# serre_light_v1.net
KiCad netlist of a schematic drawn in EAGLE
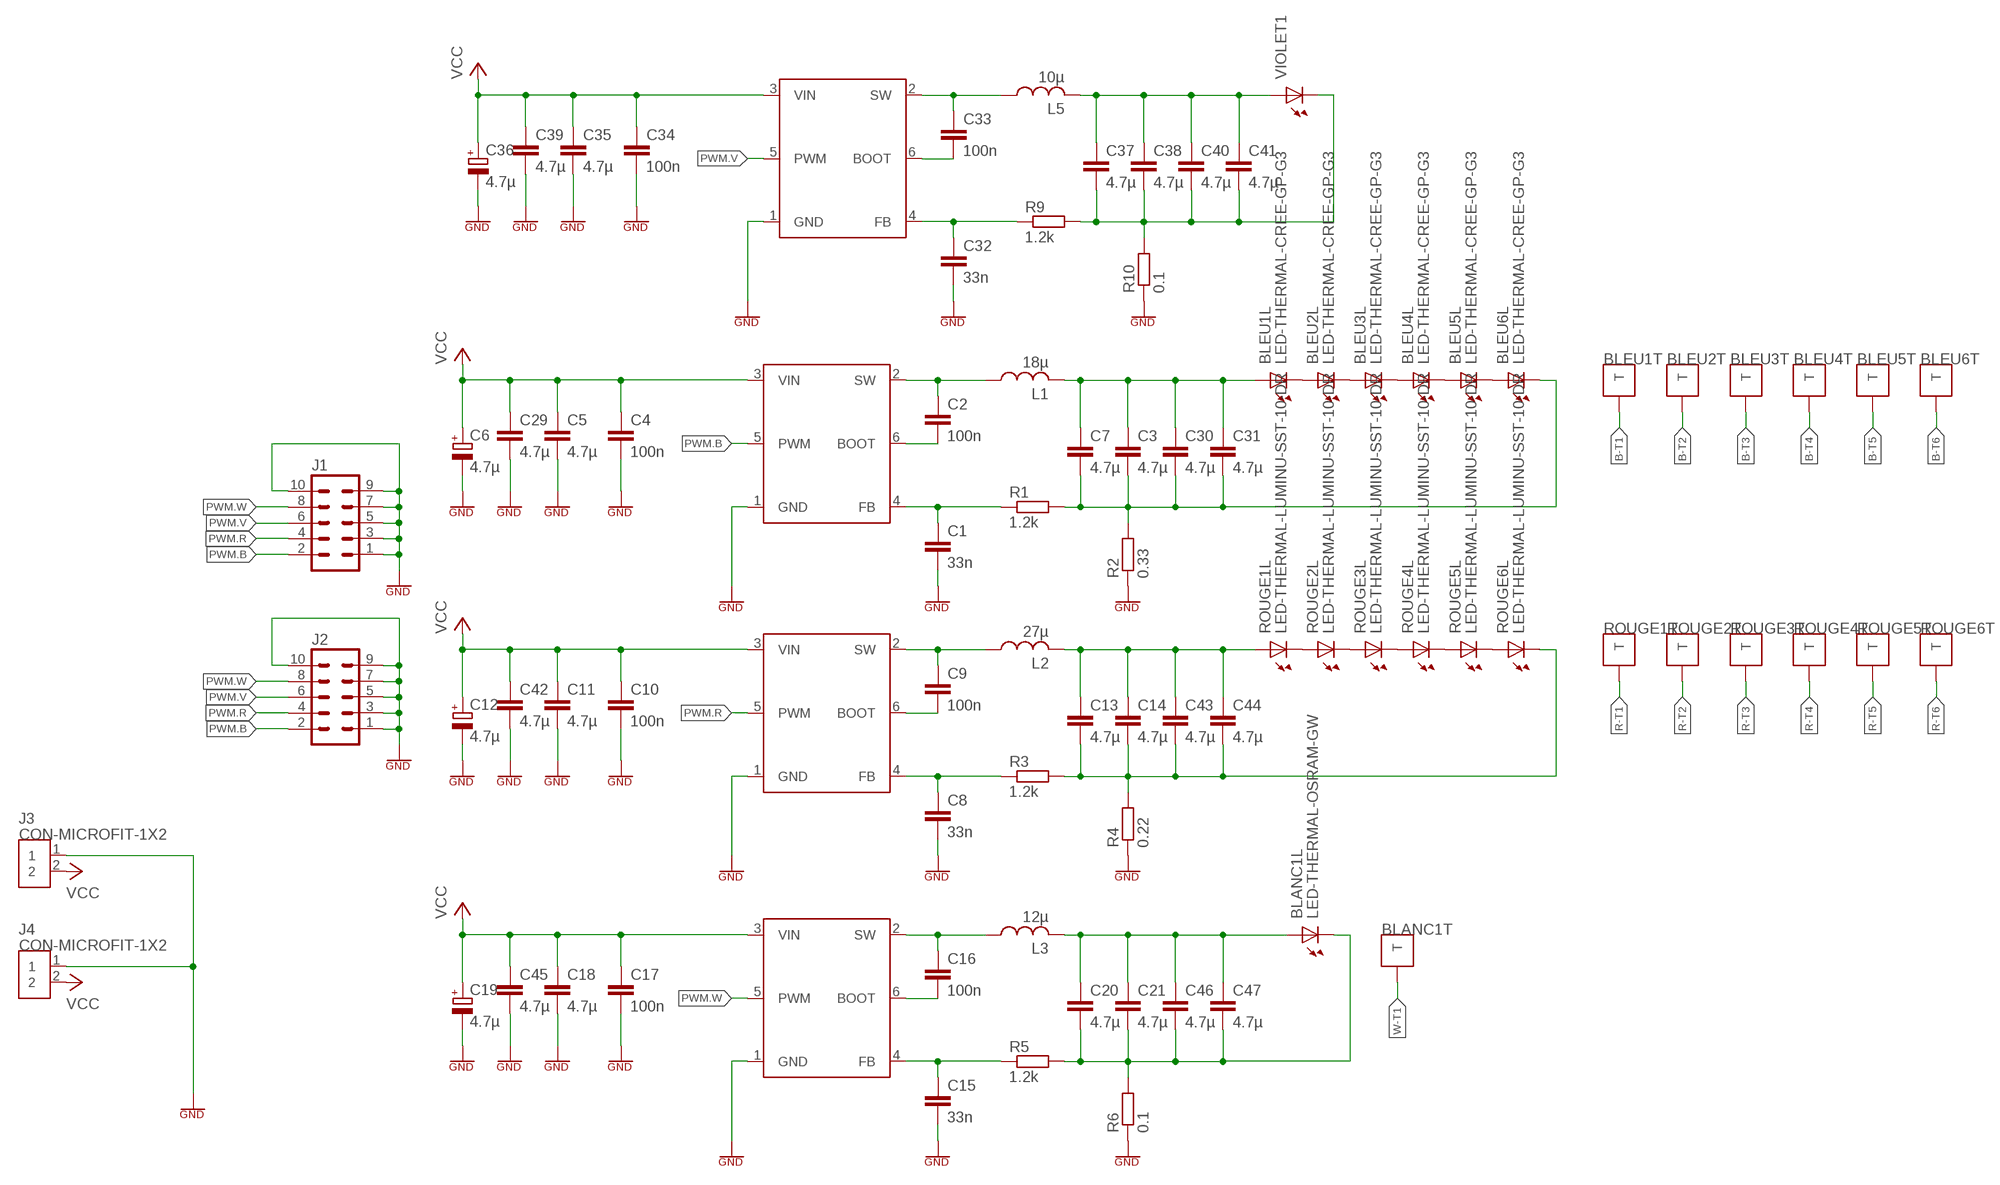
[diagram p0: schematic, sheet 1]

(export (version "E")
  (design (tool "Eeschema 10.0.6"))
  (components
    (comp (ref "BLANC1")
      (value "LED-THERMAL-OSRAM-GW")
      (footprint "eagle-import:LED-OSRAM-GW")
      (libsource (lib "eagle-import") (part "LED-THERMAL-OSRAM-GW"))
    )
    (comp (ref "BLEU1")
      (value "LED-THERMAL-CREE-GP-G3")
      (footprint "eagle-import:LED-CREE-GP-G3")
      (libsource (lib "eagle-import") (part "LED-THERMAL-CREE-GP-G3"))
    )
    (comp (ref "BLEU2")
      (value "LED-THERMAL-CREE-GP-G3")
      (footprint "eagle-import:LED-CREE-GP-G3")
      (libsource (lib "eagle-import") (part "LED-THERMAL-CREE-GP-G3"))
    )
    (comp (ref "BLEU3")
      (value "LED-THERMAL-CREE-GP-G3")
      (footprint "eagle-import:LED-CREE-GP-G3")
      (libsource (lib "eagle-import") (part "LED-THERMAL-CREE-GP-G3"))
    )
    (comp (ref "BLEU4")
      (value "LED-THERMAL-CREE-GP-G3")
      (footprint "eagle-import:LED-CREE-GP-G3")
      (libsource (lib "eagle-import") (part "LED-THERMAL-CREE-GP-G3"))
    )
    (comp (ref "BLEU5")
      (value "LED-THERMAL-CREE-GP-G3")
      (footprint "eagle-import:LED-CREE-GP-G3")
      (libsource (lib "eagle-import") (part "LED-THERMAL-CREE-GP-G3"))
    )
    (comp (ref "BLEU6")
      (value "LED-THERMAL-CREE-GP-G3")
      (footprint "eagle-import:LED-CREE-GP-G3")
      (libsource (lib "eagle-import") (part "LED-THERMAL-CREE-GP-G3"))
    )
    (comp (ref "C1")
      (value "33n")
      (footprint "eagle-import:C0603")
      (libsource (lib "eagle-import") (part "CC0603"))
    )
    (comp (ref "C2")
      (value "100n")
      (footprint "eagle-import:C0603")
      (libsource (lib "eagle-import") (part "CC0603"))
    )
    (comp (ref "C3")
      (value "4.7µ")
      (footprint "eagle-import:C1210")
      (libsource (lib "eagle-import") (part "C-EUC1210"))
    )
    (comp (ref "C4")
      (value "100n")
      (footprint "eagle-import:C0805")
      (libsource (lib "eagle-import") (part "CC0805"))
    )
    (comp (ref "C5")
      (value "4.7µ")
      (footprint "eagle-import:C1210")
      (libsource (lib "eagle-import") (part "C-EUC1210"))
    )
    (comp (ref "C6")
      (value "4.7µ")
      (footprint "eagle-import:CAP-TANT-B")
      (libsource (lib "eagle-import") (part "CPOL-B"))
    )
    (comp (ref "C7")
      (value "4.7µ")
      (footprint "eagle-import:C1210")
      (libsource (lib "eagle-import") (part "C-EUC1210"))
    )
    (comp (ref "C8")
      (value "33n")
      (footprint "eagle-import:C0603")
      (libsource (lib "eagle-import") (part "CC0603"))
    )
    (comp (ref "C9")
      (value "100n")
      (footprint "eagle-import:C0603")
      (libsource (lib "eagle-import") (part "CC0603"))
    )
    (comp (ref "C10")
      (value "100n")
      (footprint "eagle-import:C0805")
      (libsource (lib "eagle-import") (part "CC0805"))
    )
    (comp (ref "C11")
      (value "4.7µ")
      (footprint "eagle-import:C1210")
      (libsource (lib "eagle-import") (part "C-EUC1210"))
    )
    (comp (ref "C12")
      (value "4.7µ")
      (footprint "eagle-import:CAP-TANT-B")
      (libsource (lib "eagle-import") (part "CPOL-B"))
    )
    (comp (ref "C13")
      (value "4.7µ")
      (footprint "eagle-import:C1210")
      (libsource (lib "eagle-import") (part "C-EUC1210"))
    )
    (comp (ref "C14")
      (value "4.7µ")
      (footprint "eagle-import:C1210")
      (libsource (lib "eagle-import") (part "C-EUC1210"))
    )
    (comp (ref "C15")
      (value "33n")
      (footprint "eagle-import:C0603")
      (libsource (lib "eagle-import") (part "CC0603"))
    )
    (comp (ref "C16")
      (value "100n")
      (footprint "eagle-import:C0603")
      (libsource (lib "eagle-import") (part "CC0603"))
    )
    (comp (ref "C17")
      (value "100n")
      (footprint "eagle-import:C0805")
      (libsource (lib "eagle-import") (part "CC0805"))
    )
    (comp (ref "C18")
      (value "4.7µ")
      (footprint "eagle-import:C1210")
      (libsource (lib "eagle-import") (part "C-EUC1210"))
    )
    (comp (ref "C19")
      (value "4.7µ")
      (footprint "eagle-import:CAP-TANT-B")
      (libsource (lib "eagle-import") (part "CPOL-B"))
    )
    (comp (ref "C20")
      (value "4.7µ")
      (footprint "eagle-import:C1210")
      (libsource (lib "eagle-import") (part "C-EUC1210"))
    )
    (comp (ref "C21")
      (value "4.7µ")
      (footprint "eagle-import:C1210")
      (libsource (lib "eagle-import") (part "C-EUC1210"))
    )
    (comp (ref "C29")
      (value "4.7µ")
      (footprint "eagle-import:C1210")
      (libsource (lib "eagle-import") (part "C-EUC1210"))
    )
    (comp (ref "C30")
      (value "4.7µ")
      (footprint "eagle-import:C1210")
      (libsource (lib "eagle-import") (part "C-EUC1210"))
    )
    (comp (ref "C31")
      (value "4.7µ")
      (footprint "eagle-import:C1210")
      (libsource (lib "eagle-import") (part "C-EUC1210"))
    )
    (comp (ref "C32")
      (value "33n")
      (footprint "eagle-import:C0603")
      (libsource (lib "eagle-import") (part "CC0603"))
    )
    (comp (ref "C33")
      (value "100n")
      (footprint "eagle-import:C0603")
      (libsource (lib "eagle-import") (part "CC0603"))
    )
    (comp (ref "C34")
      (value "100n")
      (footprint "eagle-import:C0805")
      (libsource (lib "eagle-import") (part "CC0805"))
    )
    (comp (ref "C35")
      (value "4.7µ")
      (footprint "eagle-import:C1210")
      (libsource (lib "eagle-import") (part "C-EUC1210"))
    )
    (comp (ref "C36")
      (value "4.7µ")
      (footprint "eagle-import:CAP-TANT-B")
      (libsource (lib "eagle-import") (part "CPOL-B"))
    )
    (comp (ref "C37")
      (value "4.7µ")
      (footprint "eagle-import:C1210")
      (libsource (lib "eagle-import") (part "C-EUC1210"))
    )
    (comp (ref "C38")
      (value "4.7µ")
      (footprint "eagle-import:C1210")
      (libsource (lib "eagle-import") (part "C-EUC1210"))
    )
    (comp (ref "C39")
      (value "4.7µ")
      (footprint "eagle-import:C1210")
      (libsource (lib "eagle-import") (part "C-EUC1210"))
    )
    (comp (ref "C40")
      (value "4.7µ")
      (footprint "eagle-import:C1210")
      (libsource (lib "eagle-import") (part "C-EUC1210"))
    )
    (comp (ref "C41")
      (value "4.7µ")
      (footprint "eagle-import:C1210")
      (libsource (lib "eagle-import") (part "C-EUC1210"))
    )
    (comp (ref "C42")
      (value "4.7µ")
      (footprint "eagle-import:C1210")
      (libsource (lib "eagle-import") (part "C-EUC1210"))
    )
    (comp (ref "C43")
      (value "4.7µ")
      (footprint "eagle-import:C1210")
      (libsource (lib "eagle-import") (part "C-EUC1210"))
    )
    (comp (ref "C44")
      (value "4.7µ")
      (footprint "eagle-import:C1210")
      (libsource (lib "eagle-import") (part "C-EUC1210"))
    )
    (comp (ref "C45")
      (value "4.7µ")
      (footprint "eagle-import:C1210")
      (libsource (lib "eagle-import") (part "C-EUC1210"))
    )
    (comp (ref "C46")
      (value "4.7µ")
      (footprint "eagle-import:C1210")
      (libsource (lib "eagle-import") (part "C-EUC1210"))
    )
    (comp (ref "C47")
      (value "4.7µ")
      (footprint "eagle-import:C1210")
      (libsource (lib "eagle-import") (part "C-EUC1210"))
    )
    (comp (ref "IC1")
      (value "TPS54201")
      (footprint "eagle-import:SOT23-6")
      (libsource (lib "eagle-import") (part "TPS54201"))
    )
    (comp (ref "IC2")
      (value "TPS54201")
      (footprint "eagle-import:SOT23-6")
      (libsource (lib "eagle-import") (part "TPS54201"))
    )
    (comp (ref "IC3")
      (value "TPS54201")
      (footprint "eagle-import:SOT23-6")
      (libsource (lib "eagle-import") (part "TPS54201"))
    )
    (comp (ref "IC5")
      (value "TPS54201")
      (footprint "eagle-import:SOT23-6")
      (libsource (lib "eagle-import") (part "TPS54201"))
    )
    (comp (ref "J1")
      (value "ML10")
      (footprint "eagle-import:ML10")
      (libsource (lib "eagle-import") (part "ML10"))
    )
    (comp (ref "J2")
      (value "ML10")
      (footprint "eagle-import:ML10")
      (libsource (lib "eagle-import") (part "ML10"))
    )
    (comp (ref "J3")
      (value "CON-MICROFIT-1X2")
      (footprint "eagle-import:MICROFIT-1X2")
      (libsource (lib "eagle-import") (part "CON-MICROFIT-1X2"))
    )
    (comp (ref "J4")
      (value "CON-MICROFIT-1X2")
      (footprint "eagle-import:MICROFIT-1X2")
      (libsource (lib "eagle-import") (part "CON-MICROFIT-1X2"))
    )
    (comp (ref "L1")
      (value "18µ")
      (footprint "eagle-import:L-COILCRAFT-MSS1038")
      (libsource (lib "eagle-import") (part "L-MSS1038"))
    )
    (comp (ref "L2")
      (value "27µ")
      (footprint "eagle-import:L-COILCRAFT-MSS1038")
      (libsource (lib "eagle-import") (part "L-MSS1038"))
    )
    (comp (ref "L3")
      (value "12µ")
      (footprint "eagle-import:L-COILCRAFT-MSS1038")
      (libsource (lib "eagle-import") (part "L-MSS1038"))
    )
    (comp (ref "L5")
      (value "10µ")
      (footprint "eagle-import:L-COILCRAFT-MSS1038")
      (libsource (lib "eagle-import") (part "L-MSS1038"))
    )
    (comp (ref "R1")
      (value "1.2k")
      (footprint "eagle-import:R0805")
      (libsource (lib "eagle-import") (part "RR0805"))
    )
    (comp (ref "R2")
      (value "0.33")
      (footprint "eagle-import:R1206")
      (libsource (lib "eagle-import") (part "R-EU_R1206"))
    )
    (comp (ref "R3")
      (value "1.2k")
      (footprint "eagle-import:R0805")
      (libsource (lib "eagle-import") (part "RR0805"))
    )
    (comp (ref "R4")
      (value "0.22")
      (footprint "eagle-import:R1206")
      (libsource (lib "eagle-import") (part "R-EU_R1206"))
    )
    (comp (ref "R5")
      (value "1.2k")
      (footprint "eagle-import:R0805")
      (libsource (lib "eagle-import") (part "RR0805"))
    )
    (comp (ref "R6")
      (value "0.1")
      (footprint "eagle-import:R1206")
      (libsource (lib "eagle-import") (part "R-EU_R1206"))
    )
    (comp (ref "R9")
      (value "1.2k")
      (footprint "eagle-import:R0805")
      (libsource (lib "eagle-import") (part "RR0805"))
    )
    (comp (ref "R10")
      (value "0.1")
      (footprint "eagle-import:R1206")
      (libsource (lib "eagle-import") (part "R-EU_R1206"))
    )
    (comp (ref "ROUGE1")
      (value "LED-THERMAL-LUMINU-SST-10-DR")
      (footprint "eagle-import:LED-LUMINU-SST-10-DR")
      (libsource (lib "eagle-import") (part "LED-THERMAL-LUMINU-SST-10-DR"))
    )
    (comp (ref "ROUGE2")
      (value "LED-THERMAL-LUMINU-SST-10-DR")
      (footprint "eagle-import:LED-LUMINU-SST-10-DR")
      (libsource (lib "eagle-import") (part "LED-THERMAL-LUMINU-SST-10-DR"))
    )
    (comp (ref "ROUGE3")
      (value "LED-THERMAL-LUMINU-SST-10-DR")
      (footprint "eagle-import:LED-LUMINU-SST-10-DR")
      (libsource (lib "eagle-import") (part "LED-THERMAL-LUMINU-SST-10-DR"))
    )
    (comp (ref "ROUGE4")
      (value "LED-THERMAL-LUMINU-SST-10-DR")
      (footprint "eagle-import:LED-LUMINU-SST-10-DR")
      (libsource (lib "eagle-import") (part "LED-THERMAL-LUMINU-SST-10-DR"))
    )
    (comp (ref "ROUGE5")
      (value "LED-THERMAL-LUMINU-SST-10-DR")
      (footprint "eagle-import:LED-LUMINU-SST-10-DR")
      (libsource (lib "eagle-import") (part "LED-THERMAL-LUMINU-SST-10-DR"))
    )
    (comp (ref "ROUGE6")
      (value "LED-THERMAL-LUMINU-SST-10-DR")
      (footprint "eagle-import:LED-LUMINU-SST-10-DR")
      (libsource (lib "eagle-import") (part "LED-THERMAL-LUMINU-SST-10-DR"))
    )
    (comp (ref "VIOLET1")
      (value "LED-LUXEON-UV-U2")
      (footprint "eagle-import:LED-LUXEON-UV-U2")
      (libsource (lib "eagle-import") (part "LED-LUXEON-UV-U2"))
    )
  )
  (nets
    (net (code "1") (name "B-T1") (class "Default")
      (node (ref "BLEU1") (pin "THERMAL") (pinfunction "T_THERMAL") (pintype "bidirectional"))
    )
    (net (code "2") (name "B-T2") (class "Default")
      (node (ref "BLEU2") (pin "THERMAL") (pinfunction "T_THERMAL") (pintype "bidirectional"))
    )
    (net (code "3") (name "B-T3") (class "Default")
      (node (ref "BLEU3") (pin "THERMAL") (pinfunction "T_THERMAL") (pintype "bidirectional"))
    )
    (net (code "4") (name "B-T4") (class "Default")
      (node (ref "BLEU4") (pin "THERMAL") (pinfunction "T_THERMAL") (pintype "bidirectional"))
    )
    (net (code "5") (name "B-T5") (class "Default")
      (node (ref "BLEU5") (pin "THERMAL") (pinfunction "T_THERMAL") (pintype "bidirectional"))
    )
    (net (code "6") (name "B-T6") (class "Default")
      (node (ref "BLEU6") (pin "THERMAL") (pinfunction "T_THERMAL") (pintype "bidirectional"))
    )
    (net (code "7") (name "GND") (class "Default")
      (node (ref "C1") (pin "2") (pinfunction "2_2") (pintype "passive"))
      (node (ref "C10") (pin "2") (pinfunction "2_2") (pintype "passive"))
      (node (ref "C11") (pin "2") (pinfunction "2_2") (pintype "passive"))
      (node (ref "C12") (pin "-") (pinfunction "-_-") (pintype "passive"))
      (node (ref "C15") (pin "2") (pinfunction "2_2") (pintype "passive"))
      (node (ref "C17") (pin "2") (pinfunction "2_2") (pintype "passive"))
      (node (ref "C18") (pin "2") (pinfunction "2_2") (pintype "passive"))
      (node (ref "C19") (pin "-") (pinfunction "-_-") (pintype "passive"))
      (node (ref "C29") (pin "2") (pinfunction "2_2") (pintype "passive"))
      (node (ref "C32") (pin "2") (pinfunction "2_2") (pintype "passive"))
      (node (ref "C34") (pin "2") (pinfunction "2_2") (pintype "passive"))
      (node (ref "C35") (pin "2") (pinfunction "2_2") (pintype "passive"))
      (node (ref "C36") (pin "-") (pinfunction "-_-") (pintype "passive"))
      (node (ref "C39") (pin "2") (pinfunction "2_2") (pintype "passive"))
      (node (ref "C4") (pin "2") (pinfunction "2_2") (pintype "passive"))
      (node (ref "C42") (pin "2") (pinfunction "2_2") (pintype "passive"))
      (node (ref "C45") (pin "2") (pinfunction "2_2") (pintype "passive"))
      (node (ref "C5") (pin "2") (pinfunction "2_2") (pintype "passive"))
      (node (ref "C6") (pin "-") (pinfunction "-_-") (pintype "passive"))
      (node (ref "C8") (pin "2") (pinfunction "2_2") (pintype "passive"))
      (node (ref "IC1") (pin "1") (pinfunction "GND_1") (pintype "bidirectional"))
      (node (ref "IC2") (pin "1") (pinfunction "GND_1") (pintype "bidirectional"))
      (node (ref "IC3") (pin "1") (pinfunction "GND_1") (pintype "bidirectional"))
      (node (ref "IC5") (pin "1") (pinfunction "GND_1") (pintype "bidirectional"))
      (node (ref "J1") (pin "1") (pinfunction "1_1") (pintype "passive"))
      (node (ref "J1") (pin "10") (pinfunction "10_10") (pintype "passive"))
      (node (ref "J1") (pin "3") (pinfunction "3_3") (pintype "passive"))
      (node (ref "J1") (pin "5") (pinfunction "5_5") (pintype "passive"))
      (node (ref "J1") (pin "7") (pinfunction "7_7") (pintype "passive"))
      (node (ref "J1") (pin "9") (pinfunction "9_9") (pintype "passive"))
      (node (ref "J2") (pin "1") (pinfunction "1_1") (pintype "passive"))
      (node (ref "J2") (pin "10") (pinfunction "10_10") (pintype "passive"))
      (node (ref "J2") (pin "3") (pinfunction "3_3") (pintype "passive"))
      (node (ref "J2") (pin "5") (pinfunction "5_5") (pintype "passive"))
      (node (ref "J2") (pin "7") (pinfunction "7_7") (pintype "passive"))
      (node (ref "J2") (pin "9") (pinfunction "9_9") (pintype "passive"))
      (node (ref "J3") (pin "1") (pinfunction "1_1") (pintype "bidirectional"))
      (node (ref "J4") (pin "1") (pinfunction "1_1") (pintype "bidirectional"))
      (node (ref "R10") (pin "1") (pinfunction "1_1") (pintype "passive"))
      (node (ref "R2") (pin "1") (pinfunction "1_1") (pintype "passive"))
      (node (ref "R4") (pin "1") (pinfunction "1_1") (pintype "passive"))
      (node (ref "R6") (pin "1") (pinfunction "1_1") (pintype "passive"))
    )
    (net (code "8") (name "Net-(BLANC1-PadA)") (class "Default")
      (node (ref "BLANC1") (pin "A") (pinfunction "A_A") (pintype "passive"))
      (node (ref "C20") (pin "1") (pinfunction "1_1") (pintype "passive"))
      (node (ref "C21") (pin "1") (pinfunction "1_1") (pintype "passive"))
      (node (ref "C46") (pin "1") (pinfunction "1_1") (pintype "passive"))
      (node (ref "C47") (pin "1") (pinfunction "1_1") (pintype "passive"))
      (node (ref "L3") (pin "2") (pinfunction "2_2") (pintype "passive"))
    )
    (net (code "9") (name "Net-(BLANC1-PadC)") (class "Default")
      (node (ref "BLANC1") (pin "C") (pinfunction "C_C") (pintype "passive"))
      (node (ref "C20") (pin "2") (pinfunction "2_2") (pintype "passive"))
      (node (ref "C21") (pin "2") (pinfunction "2_2") (pintype "passive"))
      (node (ref "C46") (pin "2") (pinfunction "2_2") (pintype "passive"))
      (node (ref "C47") (pin "2") (pinfunction "2_2") (pintype "passive"))
      (node (ref "R5") (pin "2") (pinfunction "2_2") (pintype "passive"))
      (node (ref "R6") (pin "2") (pinfunction "2_2") (pintype "passive"))
    )
    (net (code "10") (name "Net-(BLEU1-PadA)") (class "Default")
      (node (ref "BLEU1") (pin "A") (pinfunction "A_A") (pintype "passive"))
      (node (ref "C3") (pin "1") (pinfunction "1_1") (pintype "passive"))
      (node (ref "C30") (pin "1") (pinfunction "1_1") (pintype "passive"))
      (node (ref "C31") (pin "1") (pinfunction "1_1") (pintype "passive"))
      (node (ref "C7") (pin "1") (pinfunction "1_1") (pintype "passive"))
      (node (ref "L1") (pin "2") (pinfunction "2_2") (pintype "passive"))
    )
    (net (code "11") (name "Net-(BLEU1-PadC)") (class "Default")
      (node (ref "BLEU1") (pin "C") (pinfunction "C_C") (pintype "passive"))
      (node (ref "BLEU2") (pin "A") (pinfunction "A_A") (pintype "passive"))
    )
    (net (code "12") (name "Net-(BLEU2-PadC)") (class "Default")
      (node (ref "BLEU2") (pin "C") (pinfunction "C_C") (pintype "passive"))
      (node (ref "BLEU3") (pin "A") (pinfunction "A_A") (pintype "passive"))
    )
    (net (code "13") (name "Net-(BLEU3-PadC)") (class "Default")
      (node (ref "BLEU3") (pin "C") (pinfunction "C_C") (pintype "passive"))
      (node (ref "BLEU4") (pin "A") (pinfunction "A_A") (pintype "passive"))
    )
    (net (code "14") (name "Net-(BLEU4-PadC)") (class "Default")
      (node (ref "BLEU4") (pin "C") (pinfunction "C_C") (pintype "passive"))
      (node (ref "BLEU5") (pin "A") (pinfunction "A_A") (pintype "passive"))
    )
    (net (code "15") (name "Net-(BLEU5-PadC)") (class "Default")
      (node (ref "BLEU5") (pin "C") (pinfunction "C_C") (pintype "passive"))
      (node (ref "BLEU6") (pin "A") (pinfunction "A_A") (pintype "passive"))
    )
    (net (code "16") (name "Net-(BLEU6-PadC)") (class "Default")
      (node (ref "BLEU6") (pin "C") (pinfunction "C_C") (pintype "passive"))
      (node (ref "C3") (pin "2") (pinfunction "2_2") (pintype "passive"))
      (node (ref "C30") (pin "2") (pinfunction "2_2") (pintype "passive"))
      (node (ref "C31") (pin "2") (pinfunction "2_2") (pintype "passive"))
      (node (ref "C7") (pin "2") (pinfunction "2_2") (pintype "passive"))
      (node (ref "R1") (pin "2") (pinfunction "2_2") (pintype "passive"))
      (node (ref "R2") (pin "2") (pinfunction "2_2") (pintype "passive"))
    )
    (net (code "17") (name "Net-(C13-Pad1)") (class "Default")
      (node (ref "C13") (pin "1") (pinfunction "1_1") (pintype "passive"))
      (node (ref "C14") (pin "1") (pinfunction "1_1") (pintype "passive"))
      (node (ref "C43") (pin "1") (pinfunction "1_1") (pintype "passive"))
      (node (ref "C44") (pin "1") (pinfunction "1_1") (pintype "passive"))
      (node (ref "L2") (pin "2") (pinfunction "2_2") (pintype "passive"))
      (node (ref "ROUGE1") (pin "A") (pinfunction "A_A") (pintype "passive"))
    )
    (net (code "18") (name "Net-(C13-Pad2)") (class "Default")
      (node (ref "C13") (pin "2") (pinfunction "2_2") (pintype "passive"))
      (node (ref "C14") (pin "2") (pinfunction "2_2") (pintype "passive"))
      (node (ref "C43") (pin "2") (pinfunction "2_2") (pintype "passive"))
      (node (ref "C44") (pin "2") (pinfunction "2_2") (pintype "passive"))
      (node (ref "R3") (pin "2") (pinfunction "2_2") (pintype "passive"))
      (node (ref "R4") (pin "2") (pinfunction "2_2") (pintype "passive"))
      (node (ref "ROUGE6") (pin "C") (pinfunction "C_C") (pintype "passive"))
    )
    (net (code "19") (name "Net-(C37-Pad1)") (class "Default")
      (node (ref "C37") (pin "1") (pinfunction "1_1") (pintype "passive"))
      (node (ref "C38") (pin "1") (pinfunction "1_1") (pintype "passive"))
      (node (ref "C40") (pin "1") (pinfunction "1_1") (pintype "passive"))
      (node (ref "C41") (pin "1") (pinfunction "1_1") (pintype "passive"))
      (node (ref "L5") (pin "2") (pinfunction "2_2") (pintype "passive"))
      (node (ref "VIOLET1") (pin "A") (pinfunction "A_A") (pintype "passive"))
    )
    (net (code "20") (name "Net-(C37-Pad2)") (class "Default")
      (node (ref "C37") (pin "2") (pinfunction "2_2") (pintype "passive"))
      (node (ref "C38") (pin "2") (pinfunction "2_2") (pintype "passive"))
      (node (ref "C40") (pin "2") (pinfunction "2_2") (pintype "passive"))
      (node (ref "C41") (pin "2") (pinfunction "2_2") (pintype "passive"))
      (node (ref "R10") (pin "2") (pinfunction "2_2") (pintype "passive"))
      (node (ref "R9") (pin "2") (pinfunction "2_2") (pintype "passive"))
      (node (ref "VIOLET1") (pin "C") (pinfunction "C_C") (pintype "passive"))
    )
    (net (code "21") (name "Net-(IC1-BOOT)") (class "Default")
      (node (ref "C2") (pin "2") (pinfunction "2_2") (pintype "passive"))
      (node (ref "IC1") (pin "6") (pinfunction "BOOT_6") (pintype "bidirectional"))
    )
    (net (code "22") (name "Net-(IC1-FB)") (class "Default")
      (node (ref "C1") (pin "1") (pinfunction "1_1") (pintype "passive"))
      (node (ref "IC1") (pin "4") (pinfunction "FB_4") (pintype "bidirectional"))
      (node (ref "R1") (pin "1") (pinfunction "1_1") (pintype "passive"))
    )
    (net (code "23") (name "Net-(IC1-SW)") (class "Default")
      (node (ref "C2") (pin "1") (pinfunction "1_1") (pintype "passive"))
      (node (ref "IC1") (pin "2") (pinfunction "SW_2") (pintype "bidirectional"))
      (node (ref "L1") (pin "1") (pinfunction "1_1") (pintype "passive"))
    )
    (net (code "24") (name "Net-(IC2-BOOT)") (class "Default")
      (node (ref "C9") (pin "2") (pinfunction "2_2") (pintype "passive"))
      (node (ref "IC2") (pin "6") (pinfunction "BOOT_6") (pintype "bidirectional"))
    )
    (net (code "25") (name "Net-(IC2-FB)") (class "Default")
      (node (ref "C8") (pin "1") (pinfunction "1_1") (pintype "passive"))
      (node (ref "IC2") (pin "4") (pinfunction "FB_4") (pintype "bidirectional"))
      (node (ref "R3") (pin "1") (pinfunction "1_1") (pintype "passive"))
    )
    (net (code "26") (name "Net-(IC2-SW)") (class "Default")
      (node (ref "C9") (pin "1") (pinfunction "1_1") (pintype "passive"))
      (node (ref "IC2") (pin "2") (pinfunction "SW_2") (pintype "bidirectional"))
      (node (ref "L2") (pin "1") (pinfunction "1_1") (pintype "passive"))
    )
    (net (code "27") (name "Net-(IC3-BOOT)") (class "Default")
      (node (ref "C16") (pin "2") (pinfunction "2_2") (pintype "passive"))
      (node (ref "IC3") (pin "6") (pinfunction "BOOT_6") (pintype "bidirectional"))
    )
    (net (code "28") (name "Net-(IC3-FB)") (class "Default")
      (node (ref "C15") (pin "1") (pinfunction "1_1") (pintype "passive"))
      (node (ref "IC3") (pin "4") (pinfunction "FB_4") (pintype "bidirectional"))
      (node (ref "R5") (pin "1") (pinfunction "1_1") (pintype "passive"))
    )
    (net (code "29") (name "Net-(IC3-SW)") (class "Default")
      (node (ref "C16") (pin "1") (pinfunction "1_1") (pintype "passive"))
      (node (ref "IC3") (pin "2") (pinfunction "SW_2") (pintype "bidirectional"))
      (node (ref "L3") (pin "1") (pinfunction "1_1") (pintype "passive"))
    )
    (net (code "30") (name "Net-(IC5-BOOT)") (class "Default")
      (node (ref "C33") (pin "2") (pinfunction "2_2") (pintype "passive"))
      (node (ref "IC5") (pin "6") (pinfunction "BOOT_6") (pintype "bidirectional"))
    )
    (net (code "31") (name "Net-(IC5-FB)") (class "Default")
      (node (ref "C32") (pin "1") (pinfunction "1_1") (pintype "passive"))
      (node (ref "IC5") (pin "4") (pinfunction "FB_4") (pintype "bidirectional"))
      (node (ref "R9") (pin "1") (pinfunction "1_1") (pintype "passive"))
    )
    (net (code "32") (name "Net-(IC5-SW)") (class "Default")
      (node (ref "C33") (pin "1") (pinfunction "1_1") (pintype "passive"))
      (node (ref "IC5") (pin "2") (pinfunction "SW_2") (pintype "bidirectional"))
      (node (ref "L5") (pin "1") (pinfunction "1_1") (pintype "passive"))
    )
    (net (code "33") (name "Net-(ROUGE1-PadC)") (class "Default")
      (node (ref "ROUGE1") (pin "C") (pinfunction "C_C") (pintype "passive"))
      (node (ref "ROUGE2") (pin "A") (pinfunction "A_A") (pintype "passive"))
    )
    (net (code "34") (name "Net-(ROUGE2-PadC)") (class "Default")
      (node (ref "ROUGE2") (pin "C") (pinfunction "C_C") (pintype "passive"))
      (node (ref "ROUGE3") (pin "A") (pinfunction "A_A") (pintype "passive"))
    )
    (net (code "35") (name "Net-(ROUGE3-PadC)") (class "Default")
      (node (ref "ROUGE3") (pin "C") (pinfunction "C_C") (pintype "passive"))
      (node (ref "ROUGE4") (pin "A") (pinfunction "A_A") (pintype "passive"))
    )
    (net (code "36") (name "Net-(ROUGE4-PadC)") (class "Default")
      (node (ref "ROUGE4") (pin "C") (pinfunction "C_C") (pintype "passive"))
      (node (ref "ROUGE5") (pin "A") (pinfunction "A_A") (pintype "passive"))
    )
    (net (code "37") (name "Net-(ROUGE5-PadC)") (class "Default")
      (node (ref "ROUGE5") (pin "C") (pinfunction "C_C") (pintype "passive"))
      (node (ref "ROUGE6") (pin "A") (pinfunction "A_A") (pintype "passive"))
    )
    (net (code "38") (name "PWM.B") (class "Default")
      (node (ref "IC1") (pin "5") (pinfunction "PWM_5") (pintype "bidirectional"))
      (node (ref "J1") (pin "2") (pinfunction "2_2") (pintype "passive"))
      (node (ref "J2") (pin "2") (pinfunction "2_2") (pintype "passive"))
    )
    (net (code "39") (name "PWM.R") (class "Default")
      (node (ref "IC2") (pin "5") (pinfunction "PWM_5") (pintype "bidirectional"))
      (node (ref "J1") (pin "4") (pinfunction "4_4") (pintype "passive"))
      (node (ref "J2") (pin "4") (pinfunction "4_4") (pintype "passive"))
    )
    (net (code "40") (name "PWM.V") (class "Default")
      (node (ref "IC5") (pin "5") (pinfunction "PWM_5") (pintype "bidirectional"))
      (node (ref "J1") (pin "6") (pinfunction "6_6") (pintype "passive"))
      (node (ref "J2") (pin "6") (pinfunction "6_6") (pintype "passive"))
    )
    (net (code "41") (name "PWM.W") (class "Default")
      (node (ref "IC3") (pin "5") (pinfunction "PWM_5") (pintype "bidirectional"))
      (node (ref "J1") (pin "8") (pinfunction "8_8") (pintype "passive"))
      (node (ref "J2") (pin "8") (pinfunction "8_8") (pintype "passive"))
    )
    (net (code "42") (name "R-T1") (class "Default")
      (node (ref "ROUGE1") (pin "THERMAL") (pinfunction "T_THERMAL") (pintype "bidirectional"))
    )
    (net (code "43") (name "R-T2") (class "Default")
      (node (ref "ROUGE2") (pin "THERMAL") (pinfunction "T_THERMAL") (pintype "bidirectional"))
    )
    (net (code "44") (name "R-T3") (class "Default")
      (node (ref "ROUGE3") (pin "THERMAL") (pinfunction "T_THERMAL") (pintype "bidirectional"))
    )
    (net (code "45") (name "R-T4") (class "Default")
      (node (ref "ROUGE4") (pin "THERMAL") (pinfunction "T_THERMAL") (pintype "bidirectional"))
    )
    (net (code "46") (name "R-T5") (class "Default")
      (node (ref "ROUGE5") (pin "THERMAL") (pinfunction "T_THERMAL") (pintype "bidirectional"))
    )
    (net (code "47") (name "R-T6") (class "Default")
      (node (ref "ROUGE6") (pin "THERMAL") (pinfunction "T_THERMAL") (pintype "bidirectional"))
    )
    (net (code "48") (name "VCC") (class "Default")
      (node (ref "C10") (pin "1") (pinfunction "1_1") (pintype "passive"))
      (node (ref "C11") (pin "1") (pinfunction "1_1") (pintype "passive"))
      (node (ref "C12") (pin "+") (pinfunction "+_+") (pintype "passive"))
      (node (ref "C17") (pin "1") (pinfunction "1_1") (pintype "passive"))
      (node (ref "C18") (pin "1") (pinfunction "1_1") (pintype "passive"))
      (node (ref "C19") (pin "+") (pinfunction "+_+") (pintype "passive"))
      (node (ref "C29") (pin "1") (pinfunction "1_1") (pintype "passive"))
      (node (ref "C34") (pin "1") (pinfunction "1_1") (pintype "passive"))
      (node (ref "C35") (pin "1") (pinfunction "1_1") (pintype "passive"))
      (node (ref "C36") (pin "+") (pinfunction "+_+") (pintype "passive"))
      (node (ref "C39") (pin "1") (pinfunction "1_1") (pintype "passive"))
      (node (ref "C4") (pin "1") (pinfunction "1_1") (pintype "passive"))
      (node (ref "C42") (pin "1") (pinfunction "1_1") (pintype "passive"))
      (node (ref "C45") (pin "1") (pinfunction "1_1") (pintype "passive"))
      (node (ref "C5") (pin "1") (pinfunction "1_1") (pintype "passive"))
      (node (ref "C6") (pin "+") (pinfunction "+_+") (pintype "passive"))
      (node (ref "IC1") (pin "3") (pinfunction "VIN_3") (pintype "bidirectional"))
      (node (ref "IC2") (pin "3") (pinfunction "VIN_3") (pintype "bidirectional"))
      (node (ref "IC3") (pin "3") (pinfunction "VIN_3") (pintype "bidirectional"))
      (node (ref "IC5") (pin "3") (pinfunction "VIN_3") (pintype "bidirectional"))
      (node (ref "J3") (pin "2") (pinfunction "2_2") (pintype "bidirectional"))
      (node (ref "J4") (pin "2") (pinfunction "2_2") (pintype "bidirectional"))
    )
    (net (code "49") (name "W-T1") (class "Default")
      (node (ref "BLANC1") (pin "THERMAL") (pinfunction "T_THERMAL") (pintype "bidirectional"))
    )
  )
)
